# LANA_TNY_00.net
KiCad netlist of a schematic drawn in Altium Designer
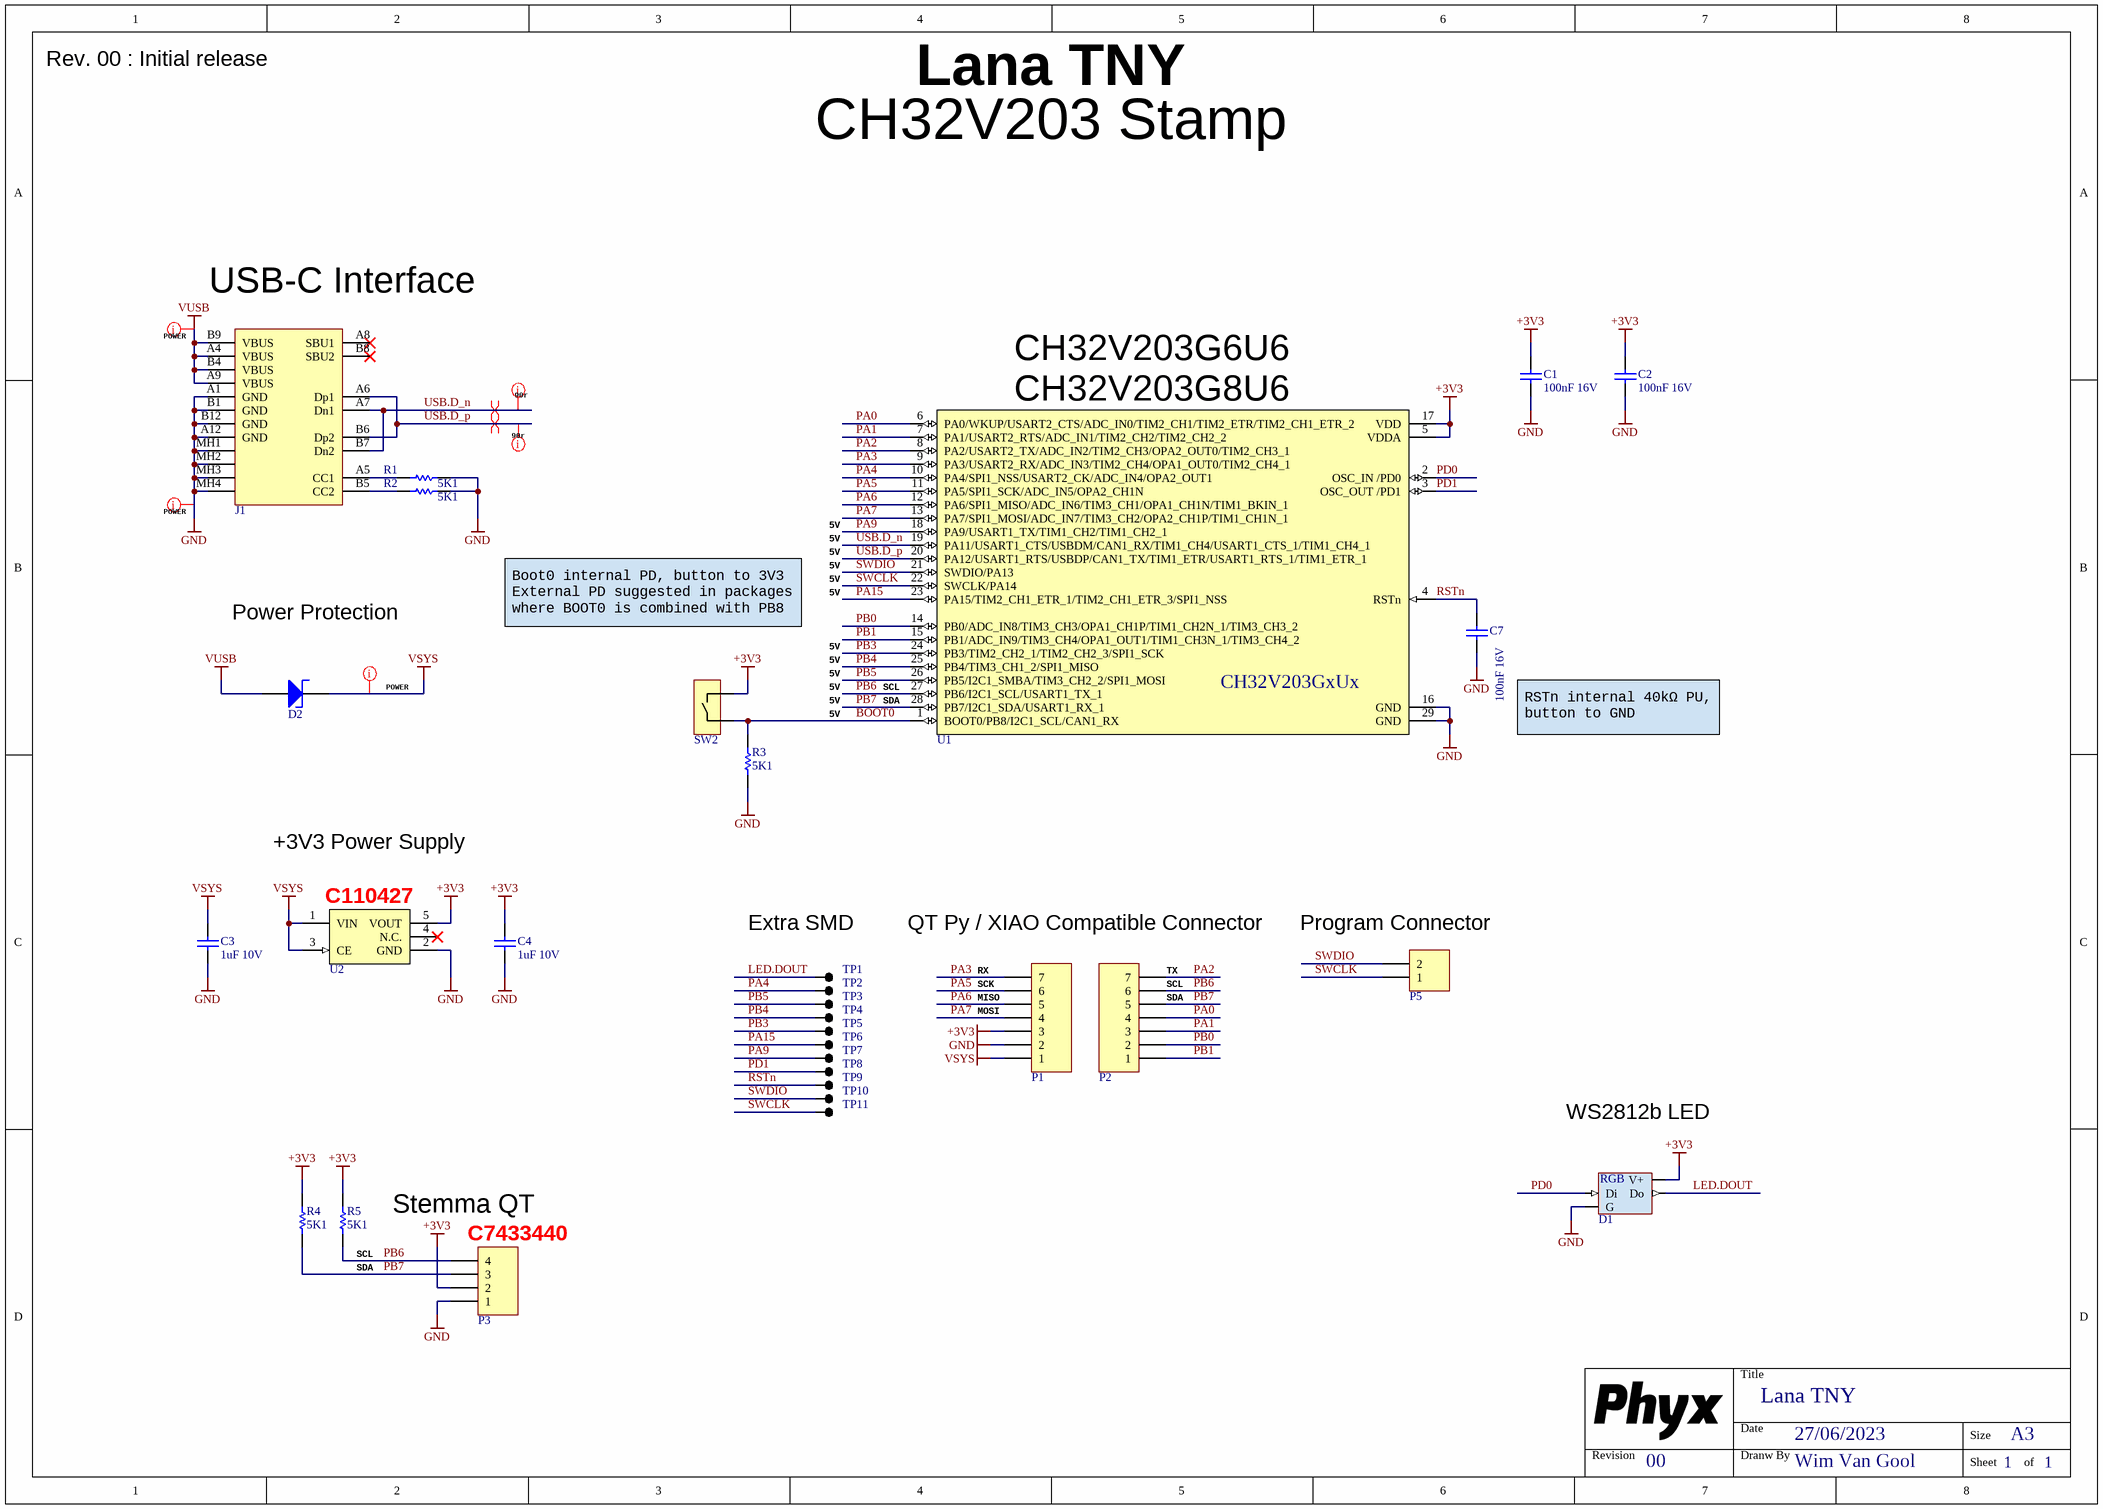
[diagram p0: LANA_TNY_00.SchDoc]

(export (version "E")
  (design (tool "Eeschema 10.0.6"))
  (components
    (comp (ref "C1")
      (value "100nF 16V")
      (footprint "C0402")
      (description "Capacitor Ceramic")
      (fields (field (name "Comment") "CAP_CERAMIC"))
      (libsource (lib "Phyx_Components") (part "CAP_CERAMIC"))
    )
    (comp (ref "C2")
      (value "100nF 16V")
      (footprint "C0402")
      (description "Capacitor Ceramic")
      (fields (field (name "Comment") "CAP_CERAMIC"))
      (libsource (lib "Phyx_Components") (part "CAP_CERAMIC"))
    )
    (comp (ref "C3")
      (value "1uF 10V")
      (footprint "C0402")
      (description "Capacitor Ceramic")
      (fields (field (name "Comment") "CAP_CERAMIC"))
      (libsource (lib "Phyx_Components") (part "CAP_CERAMIC"))
    )
    (comp (ref "C4")
      (value "1uF 10V")
      (footprint "C0402")
      (description "Capacitor Ceramic")
      (fields (field (name "Comment") "CAP_CERAMIC"))
      (libsource (lib "Phyx_Components") (part "CAP_CERAMIC"))
    )
    (comp (ref "C7")
      (value "100nF 16V")
      (footprint "C0402")
      (description "Capacitor Ceramic")
      (fields (field (name "Comment") "CAP_CERAMIC"))
      (libsource (lib "Phyx_Components") (part "CAP_CERAMIC"))
    )
    (comp (ref "D1")
      (value "WS2812 based digital RGB LED 1010 package")
      (footprint "LED_1010_WS2812B")
      (description "=Description")
      (libsource (lib "Phyx_Components") (part "LED_RGB_WS2812B_1010"))
    )
    (comp (ref "D2")
      (value "CUS10S30 Schottky Power Rectifier, 1A, 30V")
      (footprint "SOD-323_AC")
      (description "=Description")
      (libsource (lib "Phyx_Components") (part "Schottky_AC"))
    )
    (comp (ref "J1")
      (value "USB 2.0 C Reversible Receptacle Horizontal full SMD")
      (footprint "XUNPU-TYPEC-304S-ACP16")
      (libsource (lib "Phyx_Components") (part "USB_C_16_4"))
    )
    (comp (ref "P1")
      (value "Header 7")
      (footprint "HDR1X7")
      (libsource (lib "Phyx_Components") (part "Header 7"))
    )
    (comp (ref "P2") (value "Header 7") (footprint "HDR1X7") (libsource (lib "") (part "Header 7_1")))
    (comp (ref "P3")
      (value "Header 1.0mm Shrouded 4")
      (footprint "WE_665304124022")
      (libsource (lib "Phyx_Components") (part "Header 4"))
    )
    (comp (ref "P5")
      (value "Header 2")
      (footprint "HDR1X2")
      (libsource (lib "Phyx_Components") (part "Header 2"))
    )
    (comp (ref "R1")
      (value "5K1")
      (footprint "R0402")
      (fields (field (name "Comment") "RESISTOR"))
      (libsource (lib "Phyx_Components") (part "RESISTOR"))
    )
    (comp (ref "R2")
      (value "5K1")
      (footprint "R0402")
      (fields (field (name "Comment") "RESISTOR"))
      (libsource (lib "Phyx_Components") (part "RESISTOR"))
    )
    (comp (ref "R3")
      (value "5K1")
      (footprint "R0402")
      (fields (field (name "Comment") "RESISTOR"))
      (libsource (lib "Phyx_Components") (part "RESISTOR"))
    )
    (comp (ref "R4")
      (value "5K1")
      (footprint "R0402")
      (fields (field (name "Comment") "RESISTOR"))
      (libsource (lib "Phyx_Components") (part "RESISTOR"))
    )
    (comp (ref "R5")
      (value "5K1")
      (footprint "R0402")
      (fields (field (name "Comment") "RESISTOR"))
      (libsource (lib "Phyx_Components") (part "RESISTOR"))
    )
    (comp (ref "SW2")
      (value "TS24CA RA Tactile Switch 12V 50mA")
      (footprint "SHOU_HAN_TS24CA")
      (libsource (lib "Phyx_Components") (part "SW_TACT"))
    )
    (comp (ref "TP1")
      (value "TEST_PAD")
      (footprint "TP_0.4mm")
      (libsource (lib "Phyx_Components") (part "TEST_PAD"))
    )
    (comp (ref "TP2")
      (value "TEST_PAD")
      (footprint "TP_0.4mm")
      (libsource (lib "Phyx_Components") (part "TEST_PAD"))
    )
    (comp (ref "TP3")
      (value "TEST_PAD")
      (footprint "TP_0.4mm")
      (libsource (lib "Phyx_Components") (part "TEST_PAD"))
    )
    (comp (ref "TP4")
      (value "TEST_PAD")
      (footprint "TP_0.4mm")
      (libsource (lib "Phyx_Components") (part "TEST_PAD"))
    )
    (comp (ref "TP5")
      (value "TEST_PAD")
      (footprint "TP_0.4mm")
      (libsource (lib "Phyx_Components") (part "TEST_PAD"))
    )
    (comp (ref "TP6")
      (value "TEST_PAD")
      (footprint "TP_0.4mm")
      (libsource (lib "Phyx_Components") (part "TEST_PAD"))
    )
    (comp (ref "TP7")
      (value "TEST_PAD")
      (footprint "TP_0.4mm")
      (libsource (lib "Phyx_Components") (part "TEST_PAD"))
    )
    (comp (ref "TP8")
      (value "TEST_PAD")
      (footprint "TP_0.4mm")
      (libsource (lib "Phyx_Components") (part "TEST_PAD"))
    )
    (comp (ref "TP9")
      (value "TEST_PAD")
      (footprint "TP_0.4mm")
      (libsource (lib "Phyx_Components") (part "TEST_PAD"))
    )
    (comp (ref "TP10")
      (value "TEST_PAD")
      (footprint "TP_0.4mm")
      (libsource (lib "Phyx_Components") (part "TEST_PAD"))
    )
    (comp (ref "TP11")
      (value "TEST_PAD")
      (footprint "TP_0.4mm")
      (libsource (lib "Phyx_Components") (part "TEST_PAD"))
    )
    (comp (ref "U1")
      (value "WCH CH32V203G8U6 QFN28 RISC-V 32-bit MCU, 64KB Flash, 20KB RAM, USB, CAN")
      (footprint "QFN_28_4.0x4.0_P0.4")
      (libsource (lib "Phyx_Components") (part "WCH_CH32V203GxUx"))
    )
    (comp (ref "U2")
      (value "3V3 LDO 300mA 150mV")
      (footprint "SOT23-5")
      (description "=Designator")
      (libsource (lib "Phyx_Components") (part "XC6210_SOT"))
    )
  )
  (nets
    (net (code "1") (name "+3V3") (class "Default")
      (node (ref "C1") (pin "1") (pinfunction "1_1") (pintype "passive"))
      (node (ref "C2") (pin "1") (pinfunction "1_1") (pintype "passive"))
      (node (ref "C4") (pin "1") (pinfunction "1_1") (pintype "passive"))
      (node (ref "D1") (pin "2") (pinfunction "V+_2") (pintype "power_in"))
      (node (ref "P1") (pin "3") (pinfunction "3_3") (pintype "passive"))
      (node (ref "P3") (pin "2") (pinfunction "2_2") (pintype "passive"))
      (node (ref "R4") (pin "1") (pinfunction "1_1") (pintype "passive"))
      (node (ref "R5") (pin "1") (pinfunction "1_1") (pintype "passive"))
      (node (ref "SW2") (pin "1") (pinfunction "1_1") (pintype "passive"))
      (node (ref "U1") (pin "17") (pinfunction "VDD_17") (pintype "power_in"))
      (node (ref "U1") (pin "5") (pinfunction "VDDA_5") (pintype "power_in"))
      (node (ref "U2") (pin "5") (pinfunction "VOUT_5") (pintype "power_in"))
    )
    (net (code "2") (name "/BOOT0") (class "Default")
      (node (ref "R3") (pin "1") (pinfunction "1_1") (pintype "passive"))
      (node (ref "SW2") (pin "2") (pinfunction "2_2") (pintype "passive"))
      (node (ref "U1") (pin "1") (pinfunction "BOOT0/PB8/I2C1_SCL/CAN1_RX_1") (pintype "bidirectional"))
    )
    (net (code "3") (name "/LED.DOUT") (class "Default")
      (node (ref "D1") (pin "1") (pinfunction "Do_1") (pintype "output"))
      (node (ref "TP1") (pin "1") (pinfunction "1_1") (pintype "passive"))
    )
    (net (code "4") (name "/PA0") (class "Default")
      (node (ref "P2") (pin "4") (pinfunction "4_4") (pintype "passive"))
      (node (ref "U1") (pin "6") (pinfunction "PA0/WKUP/USART2_CTS/ADC_IN0/TIM2_CH1/TIM2_ETR/TIM2_CH1_ETR_2_6") (pintype "bidirectional"))
    )
    (net (code "5") (name "/PA1") (class "Default")
      (node (ref "P2") (pin "3") (pinfunction "3_3") (pintype "passive"))
      (node (ref "U1") (pin "7") (pinfunction "PA1/USART2_RTS/ADC_IN1/TIM2_CH2/TIM2_CH2_2_7") (pintype "bidirectional"))
    )
    (net (code "6") (name "/PA2") (class "Default")
      (node (ref "P2") (pin "7") (pinfunction "7_7") (pintype "passive"))
      (node (ref "U1") (pin "8") (pinfunction "PA2/USART2_TX/ADC_IN2/TIM2_CH3/OPA2_OUT0/TIM2_CH3_1_8") (pintype "bidirectional"))
    )
    (net (code "7") (name "/PA3") (class "Default")
      (node (ref "P1") (pin "7") (pinfunction "7_7") (pintype "passive"))
      (node (ref "U1") (pin "9") (pinfunction "PA3/USART2_RX/ADC_IN3/TIM2_CH4/OPA1_OUT0/TIM2_CH4_1_9") (pintype "bidirectional"))
    )
    (net (code "8") (name "/PA4") (class "Default")
      (node (ref "TP2") (pin "1") (pinfunction "1_1") (pintype "passive"))
      (node (ref "U1") (pin "10") (pinfunction "PA4/SPI1_NSS/USART2_CK/ADC_IN4/OPA2_OUT1_10") (pintype "bidirectional"))
    )
    (net (code "9") (name "/PA5") (class "Default")
      (node (ref "P1") (pin "6") (pinfunction "6_6") (pintype "passive"))
      (node (ref "U1") (pin "11") (pinfunction "PA5/SPI1_SCK/ADC_IN5/OPA2_CH1N_11") (pintype "bidirectional"))
    )
    (net (code "10") (name "/PA6") (class "Default")
      (node (ref "P1") (pin "5") (pinfunction "5_5") (pintype "passive"))
      (node (ref "U1") (pin "12") (pinfunction "PA6/SPI1_MISO/ADC_IN6/TIM3_CH1/OPA1_CH1N/TIM1_BKIN_1_12") (pintype "bidirectional"))
    )
    (net (code "11") (name "/PA7") (class "Default")
      (node (ref "P1") (pin "4") (pinfunction "4_4") (pintype "passive"))
      (node (ref "U1") (pin "13") (pinfunction "PA7/SPI1_MOSI/ADC_IN7/TIM3_CH2/OPA2_CH1P/TIM1_CH1N_1_13") (pintype "bidirectional"))
    )
    (net (code "12") (name "/PA9") (class "Default")
      (node (ref "TP7") (pin "1") (pinfunction "1_1") (pintype "passive"))
      (node (ref "U1") (pin "18") (pinfunction "PA9/USART1_TX/TIM1_CH2/TIM1_CH2_1_18") (pintype "bidirectional"))
    )
    (net (code "13") (name "/PA15") (class "Default")
      (node (ref "TP6") (pin "1") (pinfunction "1_1") (pintype "passive"))
      (node (ref "U1") (pin "23") (pinfunction "PA15/TIM2_CH1_ETR_1/TIM2_CH1_ETR_3/SPI1_NSS_23") (pintype "bidirectional"))
    )
    (net (code "14") (name "/PB0") (class "Default")
      (node (ref "P2") (pin "2") (pinfunction "2_2") (pintype "passive"))
      (node (ref "U1") (pin "14") (pinfunction "PB0/ADC_IN8/TIM3_CH3/OPA1_CH1P/TIM1_CH2N_1/TIM3_CH3_2_14") (pintype "bidirectional"))
    )
    (net (code "15") (name "/PB1") (class "Default")
      (node (ref "P2") (pin "1") (pinfunction "1_1") (pintype "passive"))
      (node (ref "U1") (pin "15") (pinfunction "PB1/ADC_IN9/TIM3_CH4/OPA1_OUT1/TIM1_CH3N_1/TIM3_CH4_2_15") (pintype "bidirectional"))
    )
    (net (code "16") (name "/PB3") (class "Default")
      (node (ref "TP5") (pin "1") (pinfunction "1_1") (pintype "passive"))
      (node (ref "U1") (pin "24") (pinfunction "PB3/TIM2_CH2_1/TIM2_CH2_3/SPI1_SCK_24") (pintype "bidirectional"))
    )
    (net (code "17") (name "/PB4") (class "Default")
      (node (ref "TP4") (pin "1") (pinfunction "1_1") (pintype "passive"))
      (node (ref "U1") (pin "25") (pinfunction "PB4/TIM3_CH1_2/SPI1_MISO_25") (pintype "bidirectional"))
    )
    (net (code "18") (name "/PB5") (class "Default")
      (node (ref "TP3") (pin "1") (pinfunction "1_1") (pintype "passive"))
      (node (ref "U1") (pin "26") (pinfunction "PB5/I2C1_SMBA/TIM3_CH2_2/SPI1_MOSI_26") (pintype "bidirectional"))
    )
    (net (code "19") (name "/PB6") (class "Default")
      (node (ref "P2") (pin "6") (pinfunction "6_6") (pintype "passive"))
      (node (ref "P3") (pin "4") (pinfunction "4_4") (pintype "passive"))
      (node (ref "R5") (pin "2") (pinfunction "2_2") (pintype "passive"))
      (node (ref "U1") (pin "27") (pinfunction "PB6/I2C1_SCL/USART1_TX_1_27") (pintype "bidirectional"))
    )
    (net (code "20") (name "/PB7") (class "Default")
      (node (ref "P2") (pin "5") (pinfunction "5_5") (pintype "passive"))
      (node (ref "P3") (pin "3") (pinfunction "3_3") (pintype "passive"))
      (node (ref "R4") (pin "2") (pinfunction "2_2") (pintype "passive"))
      (node (ref "U1") (pin "28") (pinfunction "PB7/I2C1_SDA/USART1_RX_1_28") (pintype "bidirectional"))
    )
    (net (code "21") (name "/PD0") (class "Default")
      (node (ref "D1") (pin "4") (pinfunction "Di_4") (pintype "input"))
      (node (ref "U1") (pin "2") (pinfunction "OSC_IN_/PD0_2") (pintype "bidirectional"))
    )
    (net (code "22") (name "/PD1") (class "Default")
      (node (ref "TP8") (pin "1") (pinfunction "1_1") (pintype "passive"))
      (node (ref "U1") (pin "3") (pinfunction "OSC_OUT_/PD1_3") (pintype "bidirectional"))
    )
    (net (code "23") (name "/RSTn") (class "Default")
      (node (ref "C7") (pin "1") (pinfunction "1_1") (pintype "passive"))
      (node (ref "TP9") (pin "1") (pinfunction "1_1") (pintype "passive"))
      (node (ref "U1") (pin "4") (pinfunction "RSTn_4") (pintype "input"))
    )
    (net (code "24") (name "/SWCLK") (class "Default")
      (node (ref "P5") (pin "1") (pinfunction "1_1") (pintype "passive"))
      (node (ref "TP11") (pin "1") (pinfunction "1_1") (pintype "passive"))
      (node (ref "U1") (pin "22") (pinfunction "SWCLK/PA14_22") (pintype "bidirectional"))
    )
    (net (code "25") (name "/SWDIO") (class "Default")
      (node (ref "P5") (pin "2") (pinfunction "2_2") (pintype "passive"))
      (node (ref "TP10") (pin "1") (pinfunction "1_1") (pintype "passive"))
      (node (ref "U1") (pin "21") (pinfunction "SWDIO/PA13_21") (pintype "bidirectional"))
    )
    (net (code "26") (name "/USB.D_n") (class "Default")
      (node (ref "J1") (pin "A7") (pinfunction "Dn1_A7") (pintype "passive"))
      (node (ref "J1") (pin "B7") (pinfunction "Dn2_B7") (pintype "passive"))
      (node (ref "U1") (pin "19") (pinfunction "PA11/USART1_CTS/USBDM/CAN1_RX/TIM1_CH4/USART1_CTS_1/TIM1_CH4_1_19") (pintype "bidirectional"))
    )
    (net (code "27") (name "/USB.D_p") (class "Default")
      (node (ref "J1") (pin "A6") (pinfunction "Dp1_A6") (pintype "passive"))
      (node (ref "J1") (pin "B6") (pinfunction "Dp2_B6") (pintype "passive"))
      (node (ref "U1") (pin "20") (pinfunction "PA12/USART1_RTS/USBDP/CAN1_TX/TIM1_ETR/USART1_RTS_1/TIM1_ETR_1_20") (pintype "bidirectional"))
    )
    (net (code "28") (name "GND") (class "Default")
      (node (ref "C1") (pin "2") (pinfunction "2_2") (pintype "passive"))
      (node (ref "C2") (pin "2") (pinfunction "2_2") (pintype "passive"))
      (node (ref "C3") (pin "2") (pinfunction "2_2") (pintype "passive"))
      (node (ref "C4") (pin "2") (pinfunction "2_2") (pintype "passive"))
      (node (ref "C7") (pin "2") (pinfunction "2_2") (pintype "passive"))
      (node (ref "D1") (pin "3") (pinfunction "G_3") (pintype "power_in"))
      (node (ref "J1") (pin "A1") (pinfunction "GND_A1") (pintype "passive"))
      (node (ref "J1") (pin "A12") (pinfunction "GND_A12") (pintype "passive"))
      (node (ref "J1") (pin "B1") (pinfunction "GND_B1") (pintype "passive"))
      (node (ref "J1") (pin "B12") (pinfunction "GND_B12") (pintype "passive"))
      (node (ref "J1") (pin "MH1") (pinfunction "Tab_MH1") (pintype "passive"))
      (node (ref "J1") (pin "MH2") (pinfunction "Tab_MH2") (pintype "passive"))
      (node (ref "J1") (pin "MH3") (pinfunction "Tab_MH3") (pintype "passive"))
      (node (ref "J1") (pin "MH4") (pinfunction "Tab_MH4") (pintype "passive"))
      (node (ref "P1") (pin "2") (pinfunction "2_2") (pintype "passive"))
      (node (ref "P3") (pin "1") (pinfunction "1_1") (pintype "passive"))
      (node (ref "R1") (pin "1") (pinfunction "1_1") (pintype "passive"))
      (node (ref "R2") (pin "1") (pinfunction "1_1") (pintype "passive"))
      (node (ref "R3") (pin "2") (pinfunction "2_2") (pintype "passive"))
      (node (ref "U1") (pin "16") (pinfunction "GND_16") (pintype "power_in"))
      (node (ref "U1") (pin "29") (pinfunction "GND_29") (pintype "power_in"))
      (node (ref "U2") (pin "2") (pinfunction "GND_2") (pintype "power_in"))
    )
    (net (code "29") (name "Net-(J1-CC1)") (class "Default")
      (node (ref "J1") (pin "A5") (pinfunction "CC1_A5") (pintype "passive"))
      (node (ref "R1") (pin "2") (pinfunction "2_2") (pintype "passive"))
    )
    (net (code "30") (name "Net-(J1-CC2)") (class "Default")
      (node (ref "J1") (pin "B5") (pinfunction "CC2_B5") (pintype "passive"))
      (node (ref "R2") (pin "2") (pinfunction "2_2") (pintype "passive"))
    )
    (net (code "31") (name "VSYS") (class "Default")
      (node (ref "C3") (pin "1") (pinfunction "1_1") (pintype "passive"))
      (node (ref "D2") (pin "C") (pinfunction "C_C") (pintype "passive"))
      (node (ref "P1") (pin "1") (pinfunction "1_1") (pintype "passive"))
      (node (ref "U2") (pin "1") (pinfunction "VIN_1") (pintype "power_in"))
      (node (ref "U2") (pin "3") (pinfunction "CE_3") (pintype "input"))
    )
    (net (code "32") (name "VUSB") (class "Default")
      (node (ref "D2") (pin "A") (pinfunction "A_A") (pintype "passive"))
      (node (ref "J1") (pin "A4") (pinfunction "VBUS_A4") (pintype "passive"))
      (node (ref "J1") (pin "A9") (pinfunction "VBUS_A9") (pintype "passive"))
      (node (ref "J1") (pin "B4") (pinfunction "VBUS_B4") (pintype "passive"))
      (node (ref "J1") (pin "B9") (pinfunction "VBUS_B9") (pintype "passive"))
    )
    (net (code "33") (name "unconnected-(J1-SBU1-PadA8)") (class "Default")
      (node (ref "J1") (pin "A8") (pinfunction "SBU1_A8") (pintype "passive+no_connect"))
    )
    (net (code "34") (name "unconnected-(J1-SBU2-PadB8)") (class "Default")
      (node (ref "J1") (pin "B8") (pinfunction "SBU2_B8") (pintype "passive+no_connect"))
    )
    (net (code "35") (name "unconnected-(U2-N.C.-Pad4)") (class "Default")
      (node (ref "U2") (pin "4") (pinfunction "N.C._4") (pintype "passive+no_connect"))
    )
  )
)
